# PLD_CAM_MUX.net
KiCad netlist of a schematic drawn in Altium Designer
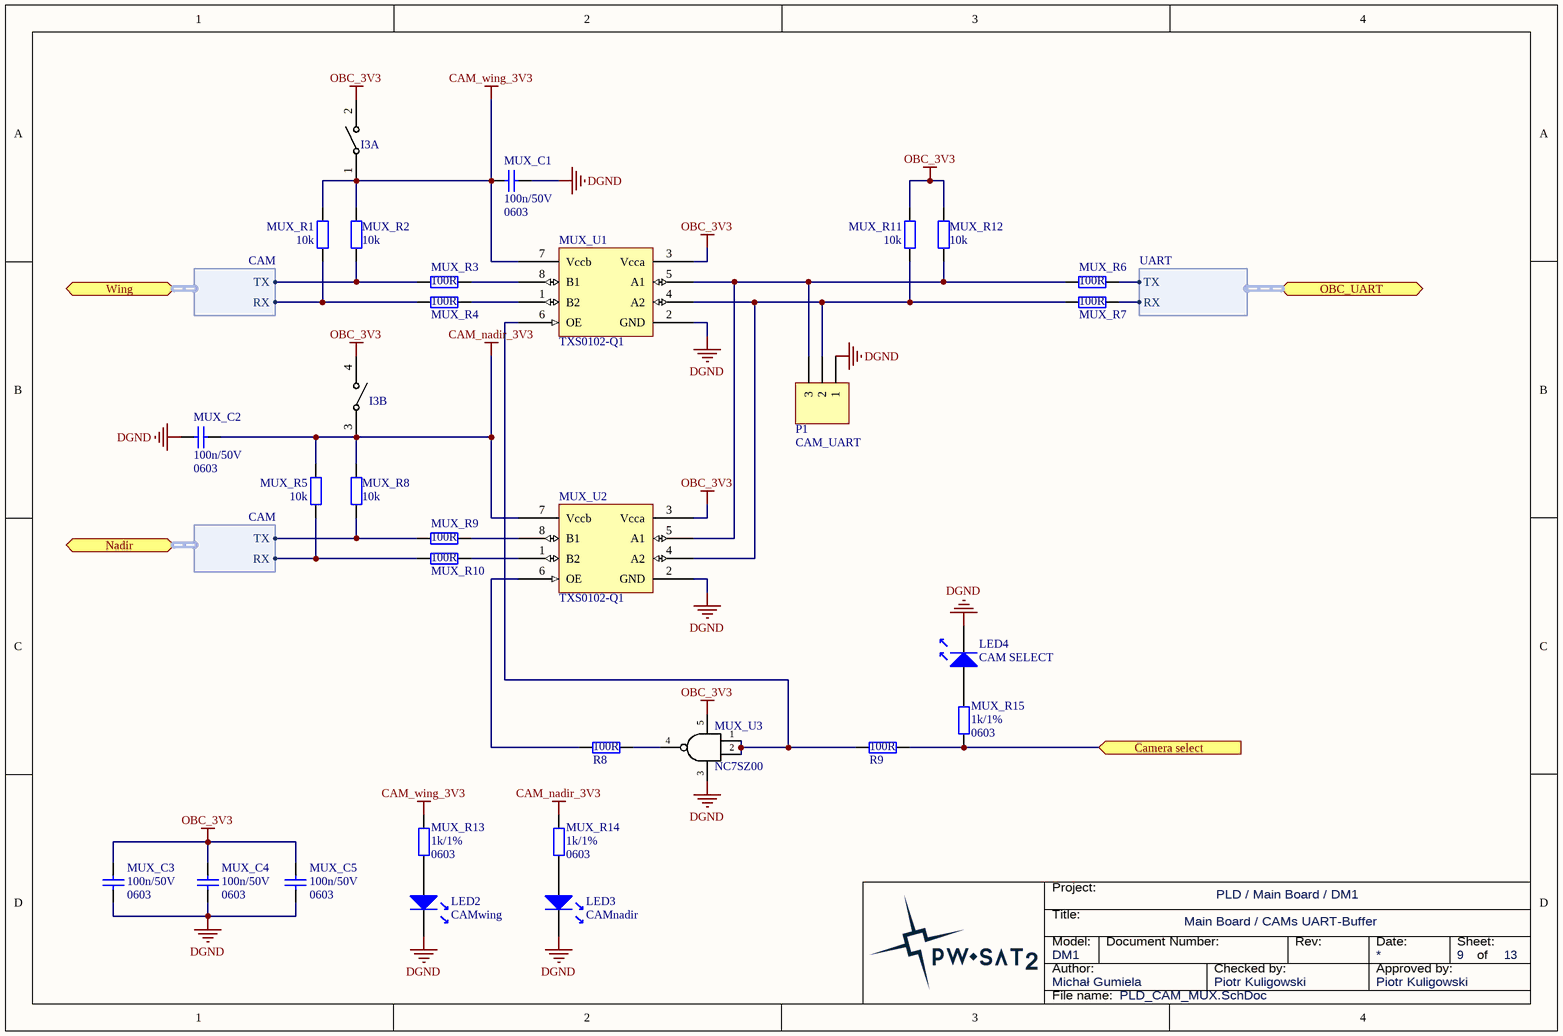
[diagram p0: PLD_CAM_MUX.SchDoc]

(export (version "E")
  (design (tool "Eeschema 10.0.6"))
  (components
    (comp (ref "I3") (value "MCEPM-02") (footprint "MCEPM-02") (libsource (lib "") (part "MCEPM-02_1")))
    (comp (ref "LED2")
      (value "CAMwing")
      (footprint "SMD_LED_1206")
      (description "LED diode, SMD1206 package.")
      (libsource (lib "diodes") (part "LED-1206_RED"))
    )
    (comp (ref "LED3")
      (value "CAMnadir")
      (footprint "SMD_LED_1206")
      (description "LED diode, SMD1206 package.")
      (libsource (lib "diodes") (part "LED-1206_RED"))
    )
    (comp (ref "LED4")
      (value "CAM SELECT")
      (footprint "SMD_LED_1206")
      (description "LED diode, SMD1206 package.")
      (libsource (lib "diodes") (part "LED-1206_RED"))
    )
    (comp (ref "MUX_C1")
      (value "100n/50V")
      (footprint "SMD_Capacitor_0603")
      (description "Ceramic Cap Kemet COTS 100n/50V X7R 0603")
      (fields
        (field (name "MANUFACTURER") "Kemet")
        (field (name "MANUFACTURERPARTNUMBER") "C0603T104K5RALTU")
        (field (name "PACKAGE") "0603")
      )
      (libsource (lib "capacitors") (part "Cer_C0603T104K5RALTU"))
    )
    (comp (ref "MUX_C2")
      (value "100n/50V")
      (footprint "SMD_Capacitor_0603")
      (description "Ceramic Cap Kemet COTS 100n/50V X7R 0603")
      (fields
        (field (name "MANUFACTURER") "Kemet")
        (field (name "MANUFACTURERPARTNUMBER") "C0603T104K5RALTU")
        (field (name "PACKAGE") "0603")
      )
      (libsource (lib "capacitors") (part "Cer_C0603T104K5RALTU"))
    )
    (comp (ref "MUX_C3")
      (value "100n/50V")
      (footprint "SMD_Capacitor_0603")
      (description "Ceramic Cap Kemet COTS 100n/50V X7R 0603")
      (fields
        (field (name "MANUFACTURER") "Kemet")
        (field (name "MANUFACTURERPARTNUMBER") "C0603T104K5RALTU")
        (field (name "PACKAGE") "0603")
      )
      (libsource (lib "capacitors") (part "Cer_C0603T104K5RALTU"))
    )
    (comp (ref "MUX_C4")
      (value "100n/50V")
      (footprint "SMD_Capacitor_0603")
      (description "Ceramic Cap Kemet COTS 100n/50V X7R 0603")
      (fields
        (field (name "MANUFACTURER") "Kemet")
        (field (name "MANUFACTURERPARTNUMBER") "C0603T104K5RALTU")
        (field (name "PACKAGE") "0603")
      )
      (libsource (lib "capacitors") (part "Cer_C0603T104K5RALTU"))
    )
    (comp (ref "MUX_C5")
      (value "100n/50V")
      (footprint "SMD_Capacitor_0603")
      (description "Ceramic Cap Kemet COTS 100n/50V X7R 0603")
      (fields
        (field (name "MANUFACTURER") "Kemet")
        (field (name "MANUFACTURERPARTNUMBER") "C0603T104K5RALTU")
        (field (name "PACKAGE") "0603")
      )
      (libsource (lib "capacitors") (part "Cer_C0603T104K5RALTU"))
    )
    (comp (ref "MUX_R1") (value "10k") (footprint "SMD_Resistor_0603") (libsource (lib "") (part "Res_1")))
    (comp (ref "MUX_R2")
      (value "10k")
      (footprint "SMD_Resistor_0603")
      (libsource (lib "resistors") (part "Res"))
    )
    (comp (ref "MUX_R3") (value "100R") (footprint "SMD_Resistor_0603") (libsource (lib "") (part "Res_1")))
    (comp (ref "MUX_R4") (value "100R") (footprint "SMD_Resistor_0603") (libsource (lib "") (part "Res_1")))
    (comp (ref "MUX_R5") (value "10k") (footprint "SMD_Resistor_0603") (libsource (lib "") (part "Res_1")))
    (comp (ref "MUX_R6") (value "100R") (footprint "SMD_Resistor_0603") (libsource (lib "") (part "Res_1")))
    (comp (ref "MUX_R7") (value "100R") (footprint "SMD_Resistor_0603") (libsource (lib "") (part "Res_1")))
    (comp (ref "MUX_R8")
      (value "10k")
      (footprint "SMD_Resistor_0603")
      (libsource (lib "resistors") (part "Res"))
    )
    (comp (ref "MUX_R9") (value "100R") (footprint "SMD_Resistor_0603") (libsource (lib "") (part "Res_1")))
    (comp (ref "MUX_R10") (value "100R") (footprint "SMD_Resistor_0603") (libsource (lib "") (part "Res_1")))
    (comp (ref "MUX_R11") (value "10k") (footprint "SMD_Resistor_0603") (libsource (lib "") (part "Res_1")))
    (comp (ref "MUX_R12")
      (value "10k")
      (footprint "SMD_Resistor_0603")
      (libsource (lib "resistors") (part "Res"))
    )
    (comp (ref "MUX_R13")
      (value "1k/1%")
      (footprint "SMD_Resistor_0603")
      (description "1k/1% Vishay CRCW 0603 Resistor. 100mW, 100ppm, 75V.")
      (fields
        (field (name "MANUFACTURER") "Vishay")
        (field (name "MANUFACTURERPARTNUMBER") "CRCW06031K00FKxxxx")
        (field (name "PACKAGE") "0603")
      )
      (libsource (lib "resistors") (part "CRCW06031K00FKxxxx"))
    )
    (comp (ref "MUX_R14")
      (value "1k/1%")
      (footprint "SMD_Resistor_0603")
      (description "1k/1% Vishay CRCW 0603 Resistor. 100mW, 100ppm, 75V.")
      (fields
        (field (name "MANUFACTURER") "Vishay")
        (field (name "MANUFACTURERPARTNUMBER") "CRCW06031K00FKxxxx")
        (field (name "PACKAGE") "0603")
      )
      (libsource (lib "resistors") (part "CRCW06031K00FKxxxx"))
    )
    (comp (ref "MUX_R15")
      (value "1k/1%")
      (footprint "SMD_Resistor_0603")
      (description "1k/1% Vishay CRCW 0603 Resistor. 100mW, 100ppm, 75V.")
      (fields
        (field (name "MANUFACTURER") "Vishay")
        (field (name "MANUFACTURERPARTNUMBER") "CRCW06031K00FKxxxx")
        (field (name "PACKAGE") "0603")
      )
      (libsource (lib "") (part "CRCW06031K00FKxxxx_1"))
    )
    (comp (ref "MUX_U1")
      (value "TXS0102-Q1")
      (footprint "VSSOP-8")
      (description "2-Bit Bidirectional Voltage-Level Translator  for Open-Drain and Push-Pull Applications")
      (fields (field (name "MANUFACTURER") "Texas Instruments"))
      (libsource (lib "microcircuits") (part "TXS0102-Q1"))
    )
    (comp (ref "MUX_U2")
      (value "TXS0102-Q1")
      (footprint "VSSOP-8")
      (description "2-Bit Bidirectional Voltage-Level Translator  for Open-Drain and Push-Pull Applications")
      (fields (field (name "MANUFACTURER") "Texas Instruments"))
      (libsource (lib "microcircuits") (part "TXS0102-Q1"))
    )
    (comp (ref "MUX_U3")
      (value "NC7SZ00")
      (footprint "SOT23-5")
      (description "TinyLogic UHS Two-Input NAND Gate.")
      (fields (field (name "MANUFACTURER") "Fairchild Semiconductor"))
      (libsource (lib "microcircuits") (part "NC7SZ00"))
    )
    (comp (ref "P1")
      (value "CAM_UART")
      (footprint "HEADER 1X3 MALE")
      (description "Header, 3-Pin")
      (fields (field (name "PUBLISHER") "Altium Limited"))
      (libsource (lib "connectors_printed-circuit-board") (part "Header 3"))
    )
    (comp (ref "R8") (value "100R") (footprint "SMD_Resistor_0603") (libsource (lib "") (part "Res_1")))
    (comp (ref "R9") (value "100R") (footprint "SMD_Resistor_0603") (libsource (lib "") (part "Res_1")))
  )
  (nets
    (net (code "3") (name "/Camera select") (class "Default")
      (node (ref "MUX_R15") (pin "1") (pinfunction "1_1") (pintype "passive"))
      (node (ref "R9") (pin "2") (pinfunction "2_2") (pintype "passive"))
    )
    (net (code "6") (name "CAM_nadir_3V3") (class "Default")
      (node (ref "I3") (pin "3") (pinfunction "3_3") (pintype "passive"))
      (node (ref "MUX_C2") (pin "1") (pinfunction "1_1") (pintype "passive"))
      (node (ref "MUX_R14") (pin "1") (pinfunction "1_1") (pintype "passive"))
      (node (ref "MUX_R5") (pin "2") (pinfunction "2_2") (pintype "passive"))
      (node (ref "MUX_R8") (pin "2") (pinfunction "2_2") (pintype "passive"))
      (node (ref "MUX_U2") (pin "7") (pinfunction "Vccb_7") (pintype "power_in"))
    )
    (net (code "7") (name "CAM_wing_3V3") (class "Default")
      (node (ref "I3") (pin "1") (pinfunction "1_1") (pintype "passive"))
      (node (ref "MUX_C1") (pin "1") (pinfunction "1_1") (pintype "passive"))
      (node (ref "MUX_R1") (pin "2") (pinfunction "2_2") (pintype "passive"))
      (node (ref "MUX_R13") (pin "1") (pinfunction "1_1") (pintype "passive"))
      (node (ref "MUX_R2") (pin "2") (pinfunction "2_2") (pintype "passive"))
      (node (ref "MUX_U1") (pin "7") (pinfunction "Vccb_7") (pintype "power_in"))
    )
    (net (code "8") (name "DGND") (class "Default")
      (node (ref "LED2") (pin "K") (pinfunction "K_K") (pintype "passive"))
      (node (ref "LED3") (pin "K") (pinfunction "K_K") (pintype "passive"))
      (node (ref "LED4") (pin "K") (pinfunction "K_K") (pintype "passive"))
      (node (ref "MUX_C1") (pin "2") (pinfunction "2_2") (pintype "passive"))
      (node (ref "MUX_C2") (pin "2") (pinfunction "2_2") (pintype "passive"))
      (node (ref "MUX_C3") (pin "2") (pinfunction "2_2") (pintype "passive"))
      (node (ref "MUX_C4") (pin "2") (pinfunction "2_2") (pintype "passive"))
      (node (ref "MUX_C5") (pin "2") (pinfunction "2_2") (pintype "passive"))
      (node (ref "MUX_U1") (pin "2") (pinfunction "GND_2") (pintype "power_in"))
      (node (ref "MUX_U2") (pin "2") (pinfunction "GND_2") (pintype "power_in"))
      (node (ref "MUX_U3") (pin "3") (pinfunction "GND_3") (pintype "passive"))
      (node (ref "P1") (pin "1") (pinfunction "1_1") (pintype "passive"))
    )
    (net (code "9") (name "Net-(LED2-PadA)") (class "Default")
      (node (ref "LED2") (pin "A") (pinfunction "A_A") (pintype "passive"))
      (node (ref "MUX_R13") (pin "2") (pinfunction "2_2") (pintype "passive"))
    )
    (net (code "10") (name "Net-(LED3-PadA)") (class "Default")
      (node (ref "LED3") (pin "A") (pinfunction "A_A") (pintype "passive"))
      (node (ref "MUX_R14") (pin "2") (pinfunction "2_2") (pintype "passive"))
    )
    (net (code "11") (name "Net-(LED4-PadA)") (class "Default")
      (node (ref "LED4") (pin "A") (pinfunction "A_A") (pintype "passive"))
      (node (ref "MUX_R15") (pin "2") (pinfunction "2_2") (pintype "passive"))
    )
    (net (code "12") (name "Net-(MUX_R1-Pad1)") (class "Default")
      (node (ref "MUX_R1") (pin "1") (pinfunction "1_1") (pintype "passive"))
      (node (ref "MUX_R4") (pin "1") (pinfunction "1_1") (pintype "passive"))
    )
    (net (code "13") (name "Net-(MUX_R2-Pad1)") (class "Default")
      (node (ref "MUX_R2") (pin "1") (pinfunction "1_1") (pintype "passive"))
      (node (ref "MUX_R3") (pin "1") (pinfunction "1_1") (pintype "passive"))
    )
    (net (code "14") (name "Net-(MUX_R8-Pad1)") (class "Default")
      (node (ref "MUX_R8") (pin "1") (pinfunction "1_1") (pintype "passive"))
      (node (ref "MUX_R9") (pin "1") (pinfunction "1_1") (pintype "passive"))
    )
    (net (code "15") (name "Net-(MUX_R10-Pad1)") (class "Default")
      (node (ref "MUX_R10") (pin "1") (pinfunction "1_1") (pintype "passive"))
      (node (ref "MUX_R5") (pin "1") (pinfunction "1_1") (pintype "passive"))
    )
    (net (code "16") (name "Net-(MUX_U1-A1)") (class "Default")
      (node (ref "MUX_R12") (pin "1") (pinfunction "1_1") (pintype "passive"))
      (node (ref "MUX_R6") (pin "1") (pinfunction "1_1") (pintype "passive"))
      (node (ref "MUX_U1") (pin "5") (pinfunction "A1_5") (pintype "bidirectional"))
      (node (ref "MUX_U2") (pin "5") (pinfunction "A1_5") (pintype "bidirectional"))
      (node (ref "P1") (pin "3") (pinfunction "3_3") (pintype "passive"))
    )
    (net (code "17") (name "Net-(MUX_U1-A2)") (class "Default")
      (node (ref "MUX_R11") (pin "1") (pinfunction "1_1") (pintype "passive"))
      (node (ref "MUX_R7") (pin "1") (pinfunction "1_1") (pintype "passive"))
      (node (ref "MUX_U1") (pin "4") (pinfunction "A2_4") (pintype "bidirectional"))
      (node (ref "MUX_U2") (pin "4") (pinfunction "A2_4") (pintype "bidirectional"))
      (node (ref "P1") (pin "2") (pinfunction "2_2") (pintype "passive"))
    )
    (net (code "18") (name "Net-(MUX_U1-B1)") (class "Default")
      (node (ref "MUX_R3") (pin "2") (pinfunction "2_2") (pintype "passive"))
      (node (ref "MUX_U1") (pin "8") (pinfunction "B1_8") (pintype "bidirectional"))
    )
    (net (code "19") (name "Net-(MUX_U1-B2)") (class "Default")
      (node (ref "MUX_R4") (pin "2") (pinfunction "2_2") (pintype "passive"))
      (node (ref "MUX_U1") (pin "1") (pinfunction "B2_1") (pintype "bidirectional"))
    )
    (net (code "20") (name "Net-(MUX_U1-OE)") (class "Default")
      (node (ref "MUX_U1") (pin "6") (pinfunction "OE_6") (pintype "input"))
      (node (ref "MUX_U3") (pin "1") (pinfunction "A_1") (pintype "passive"))
      (node (ref "MUX_U3") (pin "2") (pinfunction "B_2") (pintype "passive"))
      (node (ref "R9") (pin "1") (pinfunction "1_1") (pintype "passive"))
    )
    (net (code "21") (name "Net-(MUX_U2-B1)") (class "Default")
      (node (ref "MUX_R9") (pin "2") (pinfunction "2_2") (pintype "passive"))
      (node (ref "MUX_U2") (pin "8") (pinfunction "B1_8") (pintype "bidirectional"))
    )
    (net (code "22") (name "Net-(MUX_U2-B2)") (class "Default")
      (node (ref "MUX_R10") (pin "2") (pinfunction "2_2") (pintype "passive"))
      (node (ref "MUX_U2") (pin "1") (pinfunction "B2_1") (pintype "bidirectional"))
    )
    (net (code "23") (name "Net-(MUX_U2-OE)") (class "Default")
      (node (ref "MUX_U2") (pin "6") (pinfunction "OE_6") (pintype "input"))
      (node (ref "R8") (pin "1") (pinfunction "1_1") (pintype "passive"))
    )
    (net (code "24") (name "Net-(MUX_U3-Y)") (class "Default")
      (node (ref "MUX_U3") (pin "4") (pinfunction "Y_4") (pintype "passive"))
      (node (ref "R8") (pin "2") (pinfunction "2_2") (pintype "passive"))
    )
    (net (code "25") (name "OBC_3V3") (class "Default")
      (node (ref "I3") (pin "2") (pinfunction "2_2") (pintype "passive"))
      (node (ref "I3") (pin "4") (pinfunction "4_4") (pintype "passive"))
      (node (ref "MUX_C3") (pin "1") (pinfunction "1_1") (pintype "passive"))
      (node (ref "MUX_C4") (pin "1") (pinfunction "1_1") (pintype "passive"))
      (node (ref "MUX_C5") (pin "1") (pinfunction "1_1") (pintype "passive"))
      (node (ref "MUX_R11") (pin "2") (pinfunction "2_2") (pintype "passive"))
      (node (ref "MUX_R12") (pin "2") (pinfunction "2_2") (pintype "passive"))
      (node (ref "MUX_U1") (pin "3") (pinfunction "Vcca_3") (pintype "power_in"))
      (node (ref "MUX_U2") (pin "3") (pinfunction "Vcca_3") (pintype "power_in"))
      (node (ref "MUX_U3") (pin "5") (pinfunction "Vcc_5") (pintype "passive"))
    )
    (net (code "26") (name "unconnected-(MUX_R6-Pad2)") (class "Default")
      (node (ref "MUX_R6") (pin "2") (pinfunction "2_2") (pintype "passive"))
    )
    (net (code "27") (name "unconnected-(MUX_R7-Pad2)") (class "Default")
      (node (ref "MUX_R7") (pin "2") (pinfunction "2_2") (pintype "passive"))
    )
  )
)
